# TrinketBlinkM0C.net
KiCad netlist of a schematic drawn in EAGLE
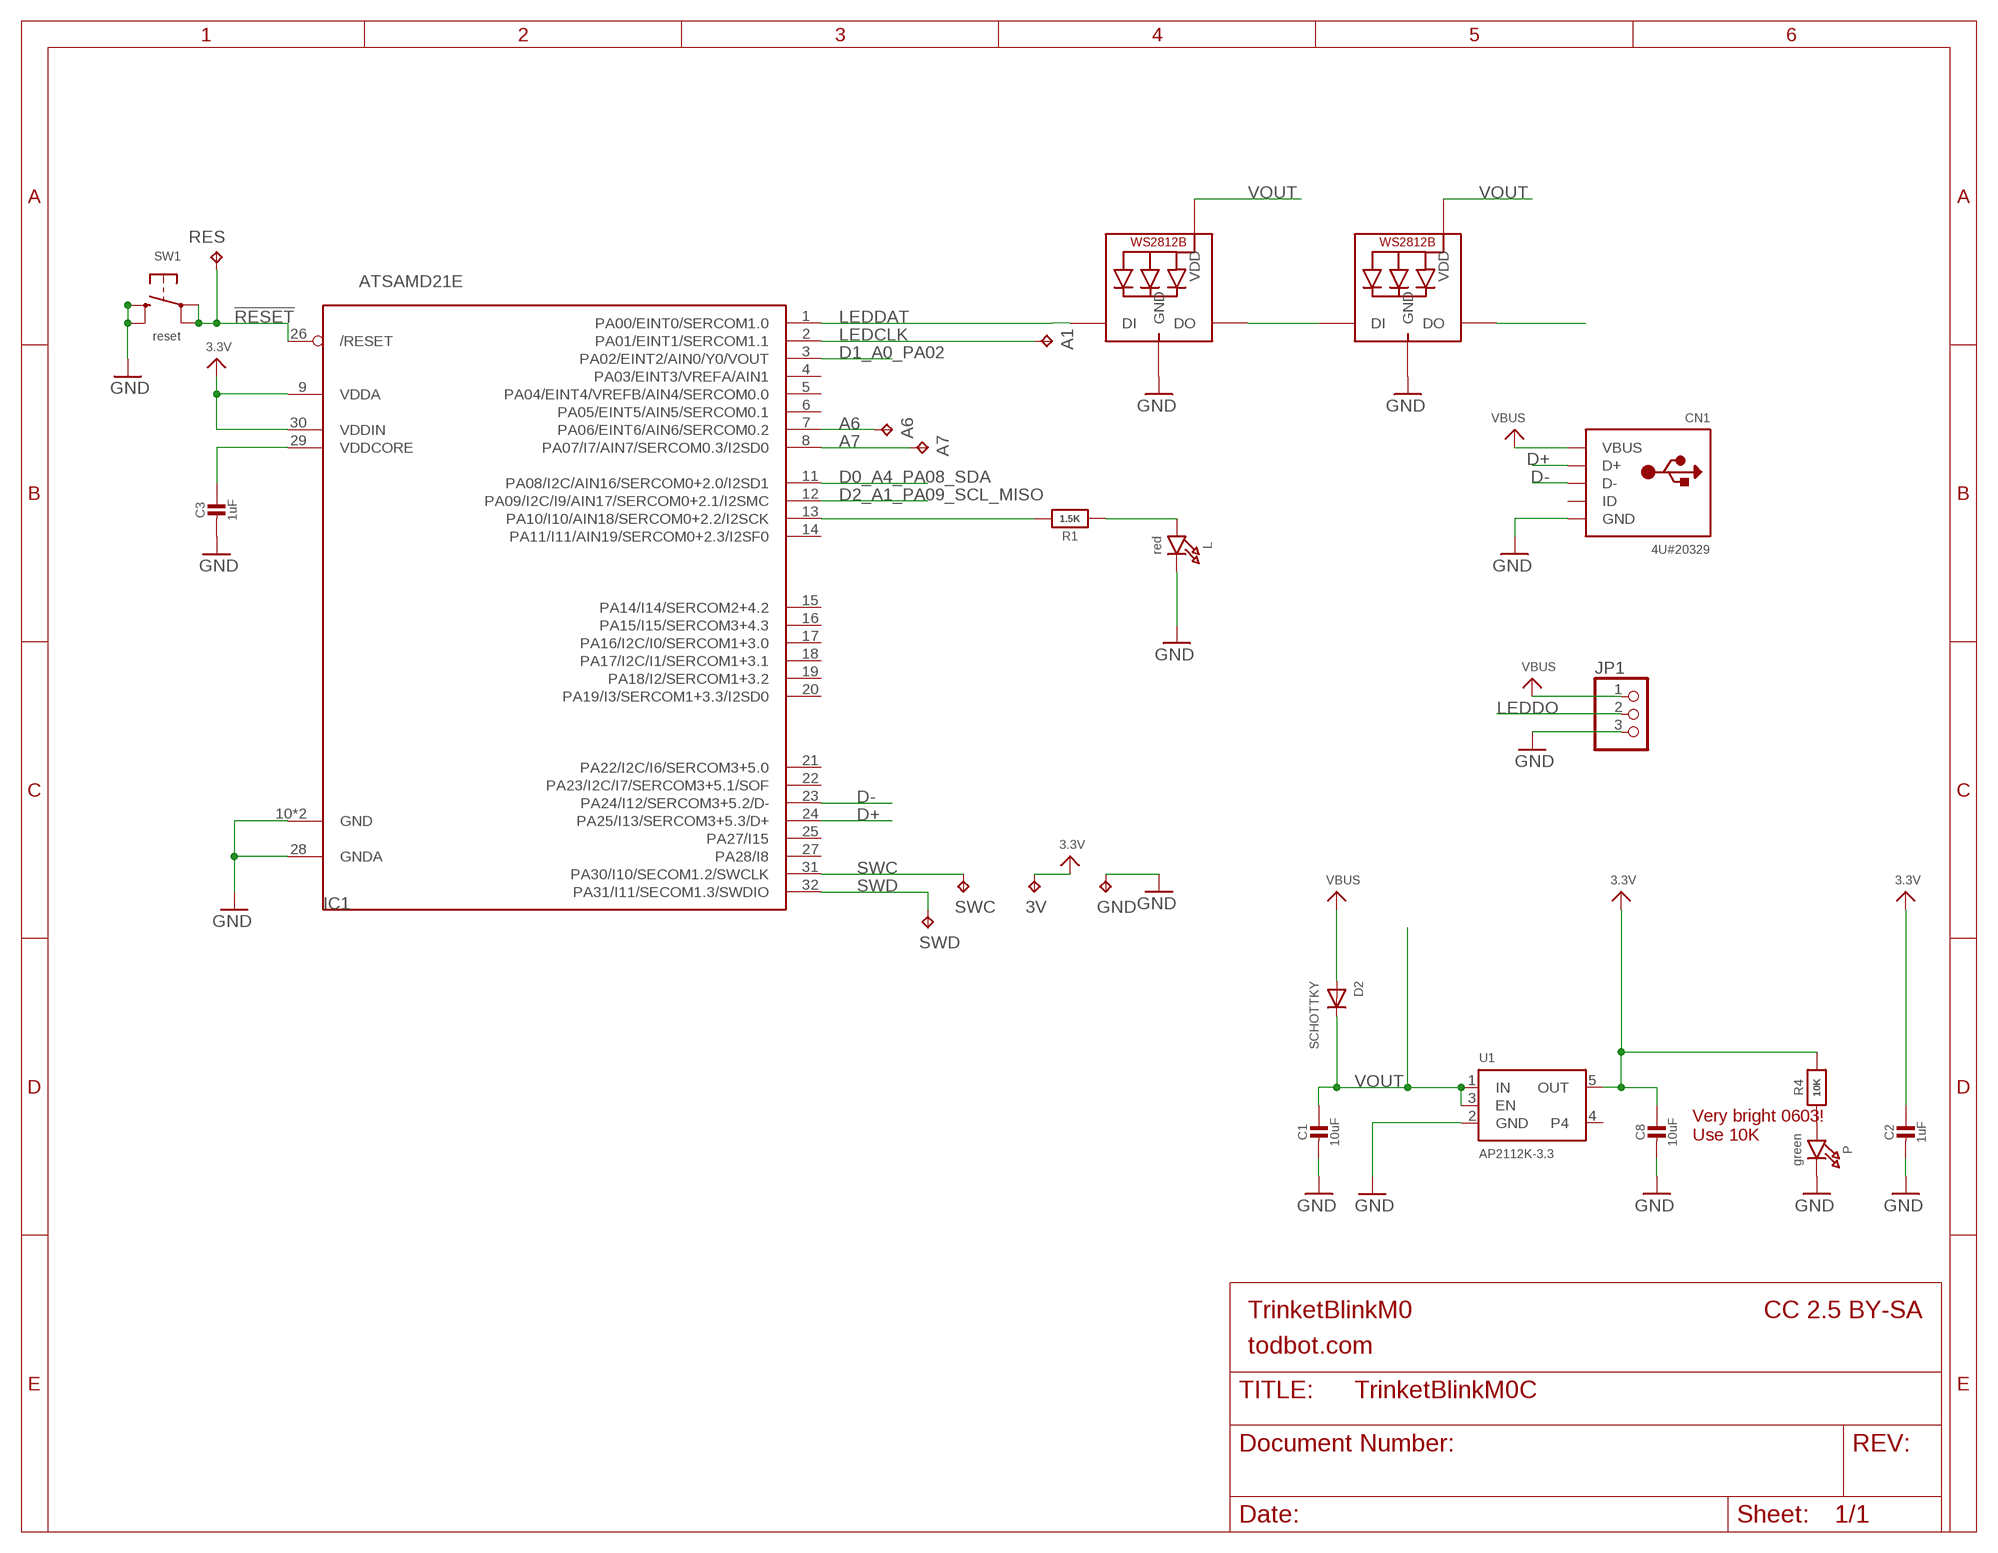
[diagram p0: schematic, sheet 1]

(export (version "E")
  (design (tool "Eeschema 10.0.6"))
  (components
    (comp (ref "3V")
      (value "TPB1,27")
      (footprint "eagle-import:B1,27")
      (libsource (lib "eagle-import") (part "TPB1,27"))
    )
    (comp (ref "A1")
      (value "TPB1,27")
      (footprint "eagle-import:B1,27")
      (libsource (lib "eagle-import") (part "TPB1,27"))
    )
    (comp (ref "A6")
      (value "TPB1,27")
      (footprint "eagle-import:B1,27")
      (libsource (lib "eagle-import") (part "TPB1,27"))
    )
    (comp (ref "A7")
      (value "TPB1,27")
      (footprint "eagle-import:B1,27")
      (libsource (lib "eagle-import") (part "TPB1,27"))
    )
    (comp (ref "C1")
      (value "10uF")
      (footprint "eagle-import:0805-NO")
      (libsource (lib "eagle-import") (part "CAP_CERAMIC0805-NOOUTLINE"))
    )
    (comp (ref "C2")
      (value "1uF")
      (footprint "eagle-import:0603-NO")
      (libsource (lib "eagle-import") (part "CAP_CERAMIC0603_NO"))
    )
    (comp (ref "C3")
      (value "1uF")
      (footprint "eagle-import:0603-NO")
      (libsource (lib "eagle-import") (part "CAP_CERAMIC0603_NO"))
    )
    (comp (ref "C8")
      (value "10uF")
      (footprint "eagle-import:0805-NO")
      (libsource (lib "eagle-import") (part "CAP_CERAMIC0805-NOOUTLINE"))
    )
    (comp (ref "CN1")
      (value "4U#20329")
      (footprint "eagle-import:4UCONN_20329_V2")
      (libsource (lib "eagle-import") (part "USB_MICRO_20329_V2"))
    )
    (comp (ref "D2")
      (value "SCHOTTKY")
      (footprint "eagle-import:SOD-123FL")
      (libsource (lib "eagle-import") (part "DIODE_SOD-123FL"))
    )
    (comp (ref "GND")
      (value "TPB1,27")
      (footprint "eagle-import:B1,27")
      (libsource (lib "eagle-import") (part "TPB1,27"))
    )
    (comp (ref "IC1")
      (value "ATSAMD21E")
      (footprint "eagle-import:QFN32_5MM")
      (libsource (lib "eagle-import") (part "ATSAMD21E"))
    )
    (comp (ref "JP1")
      (value "PINHD-1X3CB")
      (footprint "eagle-import:1X03-CLEANBIG")
      (libsource (lib "eagle-import") (part "PINHD-1X3CB"))
    )
    (comp (ref "L")
      (value "red")
      (footprint "eagle-import:CHIPLED_0603_NOOUTLINE")
      (libsource (lib "eagle-import") (part "LED0603_NOOUTLINE"))
    )
    (comp (ref "LED1")
      (value "WS2812B_5050N")
      (footprint "eagle-import:WS2812B-NARROW")
      (libsource (lib "eagle-import") (part "WS2812B_5050N"))
    )
    (comp (ref "LED2")
      (value "WS2812B_5050N")
      (footprint "eagle-import:WS2812B-NARROW")
      (libsource (lib "eagle-import") (part "WS2812B_5050N"))
    )
    (comp (ref "P")
      (value "green")
      (footprint "eagle-import:CHIPLED_0603_NOOUTLINE")
      (libsource (lib "eagle-import") (part "LED0603_NOOUTLINE"))
    )
    (comp (ref "R1")
      (value "1.5K")
      (footprint "eagle-import:0603-NO")
      (libsource (lib "eagle-import") (part "RESISTOR_0603_NOOUT"))
    )
    (comp (ref "R4")
      (value "10K")
      (footprint "eagle-import:0603-NO")
      (libsource (lib "eagle-import") (part "RESISTOR_0603_NOOUT"))
    )
    (comp (ref "RES")
      (value "TPB1,27")
      (footprint "eagle-import:B1,27")
      (libsource (lib "eagle-import") (part "TPB1,27"))
    )
    (comp (ref "SW1")
      (value "reset")
      (footprint "eagle-import:BTN_KMR2_4.6X2.8")
      (libsource (lib "eagle-import") (part "SWITCH_TACT_SMT4.6X2.8"))
    )
    (comp (ref "SWC")
      (value "TPB1,27")
      (footprint "eagle-import:B1,27")
      (libsource (lib "eagle-import") (part "TPB1,27"))
    )
    (comp (ref "SWD")
      (value "TPB1,27")
      (footprint "eagle-import:B1,27")
      (libsource (lib "eagle-import") (part "TPB1,27"))
    )
    (comp (ref "U1")
      (value "AP2112K-3.3")
      (footprint "eagle-import:SOT23-5")
      (libsource (lib "eagle-import") (part "VREG_SOT23-5"))
    )
  )
  (nets
    (net (code "1") (name "/A6") (class "Default")
      (node (ref "A6") (pin "TP") (pinfunction "TP_TP") (pintype "input"))
      (node (ref "IC1") (pin "7") (pinfunction "PA06/EINT6/AIN6/SERCOM0.2_7") (pintype "bidirectional"))
    )
    (net (code "2") (name "/A7") (class "Default")
      (node (ref "A7") (pin "TP") (pinfunction "TP_TP") (pintype "input"))
      (node (ref "IC1") (pin "8") (pinfunction "PA07/I7/AIN7/SERCOM0.3/I2SD0_8") (pintype "bidirectional"))
    )
    (net (code "3") (name "/D+") (class "Default")
      (node (ref "CN1") (pin "D+") (pinfunction "D+_D+") (pintype "bidirectional"))
      (node (ref "IC1") (pin "24") (pinfunction "PA25/I13/SERCOM3+5.3/D+_24") (pintype "bidirectional"))
    )
    (net (code "4") (name "/D-") (class "Default")
      (node (ref "CN1") (pin "D-") (pinfunction "D-_D-") (pintype "bidirectional"))
      (node (ref "IC1") (pin "23") (pinfunction "PA24/I12/SERCOM3+5.2/D-_23") (pintype "bidirectional"))
    )
    (net (code "5") (name "/D0_A4_PA08_SDA") (class "Default")
      (node (ref "IC1") (pin "11") (pinfunction "PA08/I2C/AIN16/SERCOM0+2.0/I2SD1_11") (pintype "bidirectional"))
    )
    (net (code "6") (name "/D1_A0_PA02") (class "Default")
      (node (ref "IC1") (pin "3") (pinfunction "PA02/EINT2/AIN0/Y0/VOUT_3") (pintype "bidirectional"))
    )
    (net (code "7") (name "/D2_A1_PA09_SCL_MISO") (class "Default")
      (node (ref "IC1") (pin "12") (pinfunction "PA09/I2C/I9/AIN17/SERCOM0+2.1/I2SMC_12") (pintype "bidirectional"))
    )
    (net (code "8") (name "/LEDCLK") (class "Default")
      (node (ref "A1") (pin "TP") (pinfunction "TP_TP") (pintype "input"))
      (node (ref "IC1") (pin "2") (pinfunction "PA01/EINT1/SERCOM1.1_2") (pintype "bidirectional"))
    )
    (net (code "9") (name "/LEDDAT") (class "Default")
      (node (ref "IC1") (pin "1") (pinfunction "PA00/EINT0/SERCOM1.0_1") (pintype "bidirectional"))
      (node (ref "LED1") (pin "4-DIN") (pinfunction "DI_4-DIN") (pintype "input"))
    )
    (net (code "10") (name "/LEDDO") (class "Default")
      (node (ref "JP1") (pin "2") (pinfunction "2_2") (pintype "passive"))
      (node (ref "LED2") (pin "2-DOUT") (pinfunction "DO_2-DOUT") (pintype "output"))
    )
    (net (code "11") (name "/SWC") (class "Default")
      (node (ref "IC1") (pin "31") (pinfunction "PA30/I10/SECOM1.2/SWCLK_31") (pintype "bidirectional"))
      (node (ref "SWC") (pin "TP") (pinfunction "TP_TP") (pintype "input"))
    )
    (net (code "12") (name "/SWD") (class "Default")
      (node (ref "IC1") (pin "32") (pinfunction "PA31/I11/SECOM1.3/SWDIO_32") (pintype "bidirectional"))
      (node (ref "SWD") (pin "TP") (pinfunction "TP_TP") (pintype "input"))
    )
    (net (code "13") (name "/VOUT") (class "Default")
      (node (ref "C1") (pin "1") (pinfunction "1_1") (pintype "passive"))
      (node (ref "D2") (pin "C") (pinfunction "C_C") (pintype "passive"))
      (node (ref "LED1") (pin "1-VDD") (pinfunction "VDD_1-VDD") (pintype "power_in"))
      (node (ref "LED2") (pin "1-VDD") (pinfunction "VDD_1-VDD") (pintype "power_in"))
      (node (ref "U1") (pin "1") (pinfunction "IN_1") (pintype "power_in"))
      (node (ref "U1") (pin "3") (pinfunction "EN_3") (pintype "input"))
    )
    (net (code "14") (name "/~{RESET}") (class "Default")
      (node (ref "IC1") (pin "26") (pinfunction "/RESET_26") (pintype "bidirectional"))
      (node (ref "RES") (pin "TP") (pinfunction "TP_TP") (pintype "input"))
      (node (ref "SW1") (pin "A") (pinfunction "P_A") (pintype "passive"))
      (node (ref "SW1") (pin "A'") (pinfunction "P1_A'") (pintype "passive"))
    )
    (net (code "15") (name "3.3V") (class "Default")
      (node (ref "3V") (pin "TP") (pinfunction "TP_TP") (pintype "input"))
      (node (ref "C2") (pin "1") (pinfunction "1_1") (pintype "passive"))
      (node (ref "C8") (pin "1") (pinfunction "1_1") (pintype "passive"))
      (node (ref "IC1") (pin "30") (pinfunction "VDDIN_30") (pintype "power_in"))
      (node (ref "IC1") (pin "9") (pinfunction "VDDA_9") (pintype "power_in"))
      (node (ref "R4") (pin "2") (pinfunction "2_2") (pintype "passive"))
      (node (ref "U1") (pin "5") (pinfunction "OUT_5") (pintype "power_in"))
    )
    (net (code "16") (name "GND") (class "Default")
      (node (ref "C1") (pin "2") (pinfunction "2_2") (pintype "passive"))
      (node (ref "C2") (pin "2") (pinfunction "2_2") (pintype "passive"))
      (node (ref "C3") (pin "2") (pinfunction "2_2") (pintype "passive"))
      (node (ref "C8") (pin "2") (pinfunction "2_2") (pintype "passive"))
      (node (ref "CN1") (pin "BASE@1") (pinfunction "GND_BASE@1") (pintype "power_in"))
      (node (ref "CN1") (pin "BASE@2") (pinfunction "GND_BASE@2") (pintype "power_in"))
      (node (ref "CN1") (pin "GND") (pinfunction "GND_GND") (pintype "power_in"))
      (node (ref "CN1") (pin "SPRT@1") (pinfunction "GND_SPRT@1") (pintype "power_in"))
      (node (ref "CN1") (pin "SPRT@2") (pinfunction "GND_SPRT@2") (pintype "power_in"))
      (node (ref "CN1") (pin "SPRT@3") (pinfunction "GND_SPRT@3") (pintype "power_in"))
      (node (ref "CN1") (pin "SPRT@4") (pinfunction "GND_SPRT@4") (pintype "power_in"))
      (node (ref "GND") (pin "TP") (pinfunction "TP_TP") (pintype "input"))
      (node (ref "IC1") (pin "10") (pinfunction "GND_10") (pintype "power_in"))
      (node (ref "IC1") (pin "28") (pinfunction "GNDA_28") (pintype "power_in"))
      (node (ref "IC1") (pin "33") (pinfunction "GND_33") (pintype "power_in"))
      (node (ref "JP1") (pin "3") (pinfunction "3_3") (pintype "passive"))
      (node (ref "L") (pin "C") (pinfunction "C_C") (pintype "passive"))
      (node (ref "LED1") (pin "3-GND") (pinfunction "GND_3-GND") (pintype "power_in"))
      (node (ref "LED2") (pin "3-GND") (pinfunction "GND_3-GND") (pintype "power_in"))
      (node (ref "P") (pin "C") (pinfunction "C_C") (pintype "passive"))
      (node (ref "SW1") (pin "B") (pinfunction "S_B") (pintype "passive"))
      (node (ref "SW1") (pin "B'") (pinfunction "S1_B'") (pintype "passive"))
      (node (ref "U1") (pin "2") (pinfunction "GND_2") (pintype "power_in"))
    )
    (net (code "17") (name "Net-(IC1-PA10{slash}I10{slash}AIN18{slash}SERCOM0+2.2{slash}I2SCK)") (class "Default")
      (node (ref "IC1") (pin "13") (pinfunction "PA10/I10/AIN18/SERCOM0+2.2/I2SCK_13") (pintype "bidirectional"))
      (node (ref "R1") (pin "2") (pinfunction "2_2") (pintype "passive"))
    )
    (net (code "18") (name "Net-(IC1-VDDCORE)") (class "Default")
      (node (ref "C3") (pin "1") (pinfunction "1_1") (pintype "passive"))
      (node (ref "IC1") (pin "29") (pinfunction "VDDCORE_29") (pintype "power_in"))
    )
    (net (code "19") (name "Net-(L-PadA)") (class "Default")
      (node (ref "L") (pin "A") (pinfunction "A_A") (pintype "passive"))
      (node (ref "R1") (pin "1") (pinfunction "1_1") (pintype "passive"))
    )
    (net (code "20") (name "Net-(LED1-DO)") (class "Default")
      (node (ref "LED1") (pin "2-DOUT") (pinfunction "DO_2-DOUT") (pintype "output"))
      (node (ref "LED2") (pin "4-DIN") (pinfunction "DI_4-DIN") (pintype "input"))
    )
    (net (code "21") (name "Net-(P-PadA)") (class "Default")
      (node (ref "P") (pin "A") (pinfunction "A_A") (pintype "passive"))
      (node (ref "R4") (pin "1") (pinfunction "1_1") (pintype "passive"))
    )
    (net (code "22") (name "VBUS") (class "Default")
      (node (ref "CN1") (pin "VBUS") (pinfunction "VBUS_VBUS") (pintype "power_in"))
      (node (ref "D2") (pin "A") (pinfunction "A_A") (pintype "passive"))
      (node (ref "JP1") (pin "1") (pinfunction "1_1") (pintype "passive"))
    )
    (net (code "23") (name "unconnected-(CN1-PadID)") (class "Default")
      (node (ref "CN1") (pin "ID") (pinfunction "ID_ID") (pintype "bidirectional"))
    )
    (net (code "24") (name "unconnected-(IC1-PA03{slash}EINT3{slash}VREFA{slash}AIN1-Pad4)") (class "Default")
      (node (ref "IC1") (pin "4") (pinfunction "PA03/EINT3/VREFA/AIN1_4") (pintype "bidirectional"))
    )
    (net (code "25") (name "unconnected-(IC1-PA04{slash}EINT4{slash}VREFB{slash}AIN4{slash}SERCOM0.0-Pad5)") (class "Default")
      (node (ref "IC1") (pin "5") (pinfunction "PA04/EINT4/VREFB/AIN4/SERCOM0.0_5") (pintype "bidirectional"))
    )
    (net (code "26") (name "unconnected-(IC1-PA05{slash}EINT5{slash}AIN5{slash}SERCOM0.1-Pad6)") (class "Default")
      (node (ref "IC1") (pin "6") (pinfunction "PA05/EINT5/AIN5/SERCOM0.1_6") (pintype "bidirectional"))
    )
    (net (code "27") (name "unconnected-(IC1-PA11{slash}I11{slash}AIN19{slash}SERCOM0+2.3{slash}I2SF0-Pad14)") (class "Default")
      (node (ref "IC1") (pin "14") (pinfunction "PA11/I11/AIN19/SERCOM0+2.3/I2SF0_14") (pintype "bidirectional"))
    )
    (net (code "28") (name "unconnected-(IC1-PA14{slash}I14{slash}SERCOM2+4.2-Pad15)") (class "Default")
      (node (ref "IC1") (pin "15") (pinfunction "PA14/I14/SERCOM2+4.2_15") (pintype "bidirectional"))
    )
    (net (code "29") (name "unconnected-(IC1-PA15{slash}I15{slash}SERCOM3+4.3-Pad16)") (class "Default")
      (node (ref "IC1") (pin "16") (pinfunction "PA15/I15/SERCOM3+4.3_16") (pintype "bidirectional"))
    )
    (net (code "30") (name "unconnected-(IC1-PA16{slash}I2C{slash}I0{slash}SERCOM1+3.0-Pad17)") (class "Default")
      (node (ref "IC1") (pin "17") (pinfunction "PA16/I2C/I0/SERCOM1+3.0_17") (pintype "bidirectional"))
    )
    (net (code "31") (name "unconnected-(IC1-PA17{slash}I2C{slash}I1{slash}SERCOM1+3.1-Pad18)") (class "Default")
      (node (ref "IC1") (pin "18") (pinfunction "PA17/I2C/I1/SERCOM1+3.1_18") (pintype "bidirectional"))
    )
    (net (code "32") (name "unconnected-(IC1-PA18{slash}I2{slash}SERCOM1+3.2-Pad19)") (class "Default")
      (node (ref "IC1") (pin "19") (pinfunction "PA18/I2/SERCOM1+3.2_19") (pintype "bidirectional"))
    )
    (net (code "33") (name "unconnected-(IC1-PA19{slash}I3{slash}SERCOM1+3.3{slash}I2SD0-Pad20)") (class "Default")
      (node (ref "IC1") (pin "20") (pinfunction "PA19/I3/SERCOM1+3.3/I2SD0_20") (pintype "bidirectional"))
    )
    (net (code "34") (name "unconnected-(IC1-PA22{slash}I2C{slash}I6{slash}SERCOM3+5.0-Pad21)") (class "Default")
      (node (ref "IC1") (pin "21") (pinfunction "PA22/I2C/I6/SERCOM3+5.0_21") (pintype "bidirectional"))
    )
    (net (code "35") (name "unconnected-(IC1-PA23{slash}I2C{slash}I7{slash}SERCOM3+5.1{slash}SOF-Pad22)") (class "Default")
      (node (ref "IC1") (pin "22") (pinfunction "PA23/I2C/I7/SERCOM3+5.1/SOF_22") (pintype "bidirectional"))
    )
    (net (code "36") (name "unconnected-(IC1-PA27{slash}I15-Pad25)") (class "Default")
      (node (ref "IC1") (pin "25") (pinfunction "PA27/I15_25") (pintype "bidirectional"))
    )
    (net (code "37") (name "unconnected-(IC1-PA28{slash}I8-Pad27)") (class "Default")
      (node (ref "IC1") (pin "27") (pinfunction "PA28/I8_27") (pintype "bidirectional"))
    )
    (net (code "38") (name "unconnected-(U1-P4-Pad4)") (class "Default")
      (node (ref "U1") (pin "4") (pinfunction "P4_4") (pintype "bidirectional"))
    )
  )
)
